# current_sense.net
KiCad netlist of a schematic drawn in EAGLE
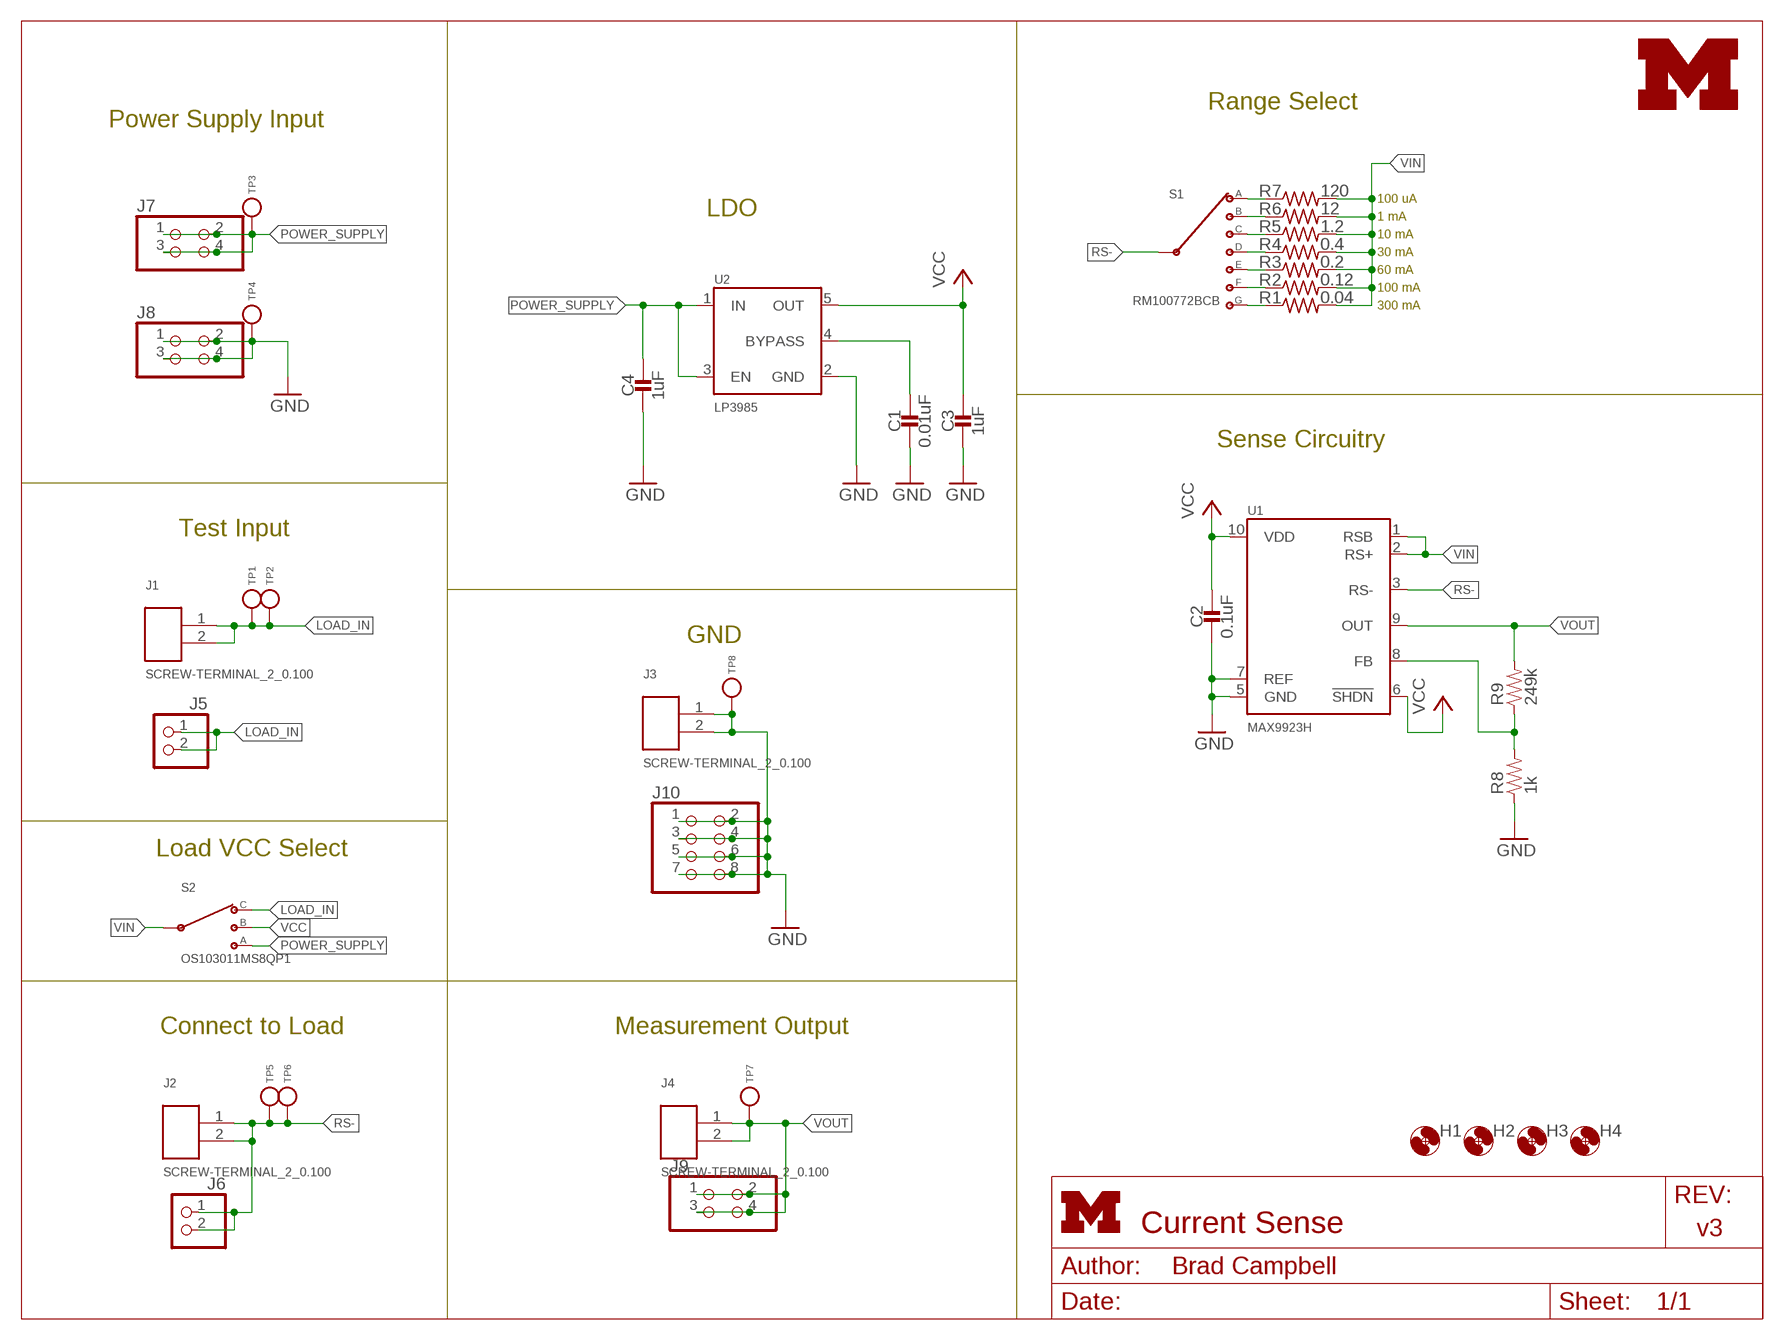
[diagram p0: schematic, sheet 1]

(export (version "E")
  (design (tool "Eeschema 10.0.6"))
  (components
    (comp (ref "C1")
      (value "0.01uF")
      (footprint "eagle-import:0603_CAP")
      (libsource (lib "eagle-import") (part "CAPACITOR0603_CAP"))
    )
    (comp (ref "C2")
      (value "0.1uF")
      (footprint "eagle-import:0603_CAP")
      (libsource (lib "eagle-import") (part "CAPACITOR0603_CAP"))
    )
    (comp (ref "C3")
      (value "1uF")
      (footprint "eagle-import:0603_CAP")
      (libsource (lib "eagle-import") (part "CAPACITOR0603_CAP"))
    )
    (comp (ref "C4")
      (value "1uF")
      (footprint "eagle-import:0603_CAP")
      (libsource (lib "eagle-import") (part "CAPACITOR0603_CAP"))
    )
    (comp (ref "H1")
      (value "MOUNT-HOLE3.2")
      (footprint "eagle-import:3,2")
      (libsource (lib "eagle-import") (part "MOUNT-HOLE3.2"))
    )
    (comp (ref "H2")
      (value "MOUNT-HOLE3.2")
      (footprint "eagle-import:3,2")
      (libsource (lib "eagle-import") (part "MOUNT-HOLE3.2"))
    )
    (comp (ref "H3")
      (value "MOUNT-HOLE3.2")
      (footprint "eagle-import:3,2")
      (libsource (lib "eagle-import") (part "MOUNT-HOLE3.2"))
    )
    (comp (ref "H4")
      (value "MOUNT-HOLE3.2")
      (footprint "eagle-import:3,2")
      (libsource (lib "eagle-import") (part "MOUNT-HOLE3.2"))
    )
    (comp (ref "J1")
      (value "SCREW-TERMINAL_2_0.100")
      (footprint "eagle-import:CONN_BLOCK_2")
      (libsource (lib "eagle-import") (part "SCREW-TERMINAL_2_0.100"))
    )
    (comp (ref "J2")
      (value "SCREW-TERMINAL_2_0.100")
      (footprint "eagle-import:CONN_BLOCK_2")
      (libsource (lib "eagle-import") (part "SCREW-TERMINAL_2_0.100"))
    )
    (comp (ref "J3")
      (value "SCREW-TERMINAL_2_0.100")
      (footprint "eagle-import:CONN_BLOCK_2")
      (libsource (lib "eagle-import") (part "SCREW-TERMINAL_2_0.100"))
    )
    (comp (ref "J4")
      (value "SCREW-TERMINAL_2_0.100")
      (footprint "eagle-import:CONN_BLOCK_2")
      (libsource (lib "eagle-import") (part "SCREW-TERMINAL_2_0.100"))
    )
    (comp (ref "J5")
      (value "PINHD-1X2")
      (footprint "eagle-import:1X02")
      (libsource (lib "eagle-import") (part "PINHD-1X2"))
    )
    (comp (ref "J6")
      (value "PINHD-1X2")
      (footprint "eagle-import:1X02")
      (libsource (lib "eagle-import") (part "PINHD-1X2"))
    )
    (comp (ref "J7")
      (value "PINHD-2X2")
      (footprint "eagle-import:2X02")
      (libsource (lib "eagle-import") (part "PINHD-2X2"))
    )
    (comp (ref "J8")
      (value "PINHD-2X2")
      (footprint "eagle-import:2X02")
      (libsource (lib "eagle-import") (part "PINHD-2X2"))
    )
    (comp (ref "J9")
      (value "PINHD-2X2")
      (footprint "eagle-import:2X02")
      (libsource (lib "eagle-import") (part "PINHD-2X2"))
    )
    (comp (ref "J10")
      (value "PINHD-2X4")
      (footprint "eagle-import:2X04")
      (libsource (lib "eagle-import") (part "PINHD-2X4"))
    )
    (comp (ref "LOGO2")
      (value "UMICH_SOLID_MEDIUM")
      (footprint "eagle-import:UMICH_SOLID_200MIL")
      (libsource (lib "eagle-import") (part "UMICH_SOLID_MEDIUM"))
    )
    (comp (ref "R1")
      (value "0.04")
      (footprint "eagle-import:R1206")
      (libsource (lib "eagle-import") (part "R-US_R1206"))
    )
    (comp (ref "R2")
      (value "0.12")
      (footprint "eagle-import:R1206")
      (libsource (lib "eagle-import") (part "R-US_R1206"))
    )
    (comp (ref "R3")
      (value "0.2")
      (footprint "eagle-import:R1206")
      (libsource (lib "eagle-import") (part "R-US_R1206"))
    )
    (comp (ref "R4")
      (value "0.4")
      (footprint "eagle-import:R1206")
      (libsource (lib "eagle-import") (part "R-US_R1206"))
    )
    (comp (ref "R5")
      (value "1.2")
      (footprint "eagle-import:R0805")
      (libsource (lib "eagle-import") (part "R-US_R0805"))
    )
    (comp (ref "R6")
      (value "12")
      (footprint "eagle-import:R0805")
      (libsource (lib "eagle-import") (part "R-US_R0805"))
    )
    (comp (ref "R7")
      (value "120")
      (footprint "eagle-import:R0805")
      (libsource (lib "eagle-import") (part "R-US_R0805"))
    )
    (comp (ref "R8")
      (value "1k")
      (footprint "eagle-import:0603-RES")
      (libsource (lib "eagle-import") (part "RESISTOR0603_RES"))
    )
    (comp (ref "R9")
      (value "249k")
      (footprint "eagle-import:0603-RES")
      (libsource (lib "eagle-import") (part "RESISTOR0603_RES"))
    )
    (comp (ref "S1")
      (value "RM100772BCB")
      (footprint "eagle-import:RM-SWITCH")
      (libsource (lib "eagle-import") (part "RM100772BCB"))
    )
    (comp (ref "S2")
      (value "OS103011MS8QP1")
      (footprint "eagle-import:OS102011MS8QP1")
      (libsource (lib "eagle-import") (part "OS103011MS8QP1"))
    )
    (comp (ref "TP1")
      (value "TEST_POINT_0.040IN")
      (footprint "eagle-import:TESTPOINT_0.040IN")
      (libsource (lib "eagle-import") (part "TEST_POINT_0.040IN"))
    )
    (comp (ref "TP2")
      (value "TEST_POINT_0.040IN")
      (footprint "eagle-import:TESTPOINT_0.040IN")
      (libsource (lib "eagle-import") (part "TEST_POINT_0.040IN"))
    )
    (comp (ref "TP3")
      (value "TEST_POINT_0.040IN")
      (footprint "eagle-import:TESTPOINT_0.040IN")
      (libsource (lib "eagle-import") (part "TEST_POINT_0.040IN"))
    )
    (comp (ref "TP4")
      (value "TEST_POINT_0.040IN")
      (footprint "eagle-import:TESTPOINT_0.040IN")
      (libsource (lib "eagle-import") (part "TEST_POINT_0.040IN"))
    )
    (comp (ref "TP5")
      (value "TEST_POINT_0.040IN")
      (footprint "eagle-import:TESTPOINT_0.040IN")
      (libsource (lib "eagle-import") (part "TEST_POINT_0.040IN"))
    )
    (comp (ref "TP6")
      (value "TEST_POINT_0.040IN")
      (footprint "eagle-import:TESTPOINT_0.040IN")
      (libsource (lib "eagle-import") (part "TEST_POINT_0.040IN"))
    )
    (comp (ref "TP7")
      (value "TEST_POINT_0.040IN")
      (footprint "eagle-import:TESTPOINT_0.040IN")
      (libsource (lib "eagle-import") (part "TEST_POINT_0.040IN"))
    )
    (comp (ref "TP8")
      (value "TEST_POINT_0.112IN")
      (footprint "eagle-import:TESTPOINT_0.112IN")
      (libsource (lib "eagle-import") (part "TEST_POINT_0.112IN"))
    )
    (comp (ref "U1")
      (value "MAX9923H")
      (footprint "eagle-import:UMAX10")
      (fields (field (name "DIGIKEY") "MAX9922EUB+TCT-ND"))
      (libsource (lib "eagle-import") (part "MAX9923H"))
    )
    (comp (ref "U2")
      (value "LP3985")
      (footprint "eagle-import:R-PDSO-G5")
      (libsource (lib "eagle-import") (part "LP3985"))
    )
  )
  (nets
    (net (code "1") (name "GND") (class "Default")
      (node (ref "C1") (pin "2") (pinfunction "2_2") (pintype "bidirectional"))
      (node (ref "C2") (pin "2") (pinfunction "2_2") (pintype "bidirectional"))
      (node (ref "C3") (pin "2") (pinfunction "2_2") (pintype "bidirectional"))
      (node (ref "C4") (pin "2") (pinfunction "2_2") (pintype "bidirectional"))
      (node (ref "J10") (pin "1") (pinfunction "1_1") (pintype "passive"))
      (node (ref "J10") (pin "2") (pinfunction "2_2") (pintype "passive"))
      (node (ref "J10") (pin "3") (pinfunction "3_3") (pintype "passive"))
      (node (ref "J10") (pin "4") (pinfunction "4_4") (pintype "passive"))
      (node (ref "J10") (pin "5") (pinfunction "5_5") (pintype "passive"))
      (node (ref "J10") (pin "6") (pinfunction "6_6") (pintype "passive"))
      (node (ref "J10") (pin "7") (pinfunction "7_7") (pintype "passive"))
      (node (ref "J10") (pin "8") (pinfunction "8_8") (pintype "passive"))
      (node (ref "J3") (pin "1") (pinfunction "1_1") (pintype "bidirectional"))
      (node (ref "J3") (pin "2") (pinfunction "2_2") (pintype "bidirectional"))
      (node (ref "J8") (pin "1") (pinfunction "1_1") (pintype "passive"))
      (node (ref "J8") (pin "2") (pinfunction "2_2") (pintype "passive"))
      (node (ref "J8") (pin "3") (pinfunction "3_3") (pintype "passive"))
      (node (ref "J8") (pin "4") (pinfunction "4_4") (pintype "passive"))
      (node (ref "R8") (pin "1") (pinfunction "1_1") (pintype "passive"))
      (node (ref "TP4") (pin "TESTPOINT") (pinfunction "TESTPOINT_TESTPOINT") (pintype "bidirectional"))
      (node (ref "TP8") (pin "1") (pinfunction "TESTPOINT_1") (pintype "bidirectional"))
      (node (ref "U1") (pin "5") (pinfunction "GND_5") (pintype "bidirectional"))
      (node (ref "U1") (pin "7") (pinfunction "REF_7") (pintype "bidirectional"))
      (node (ref "U2") (pin "2") (pinfunction "GND_2") (pintype "bidirectional"))
    )
    (net (code "2") (name "LOAD_IN") (class "Default")
      (node (ref "J1") (pin "1") (pinfunction "1_1") (pintype "bidirectional"))
      (node (ref "J1") (pin "2") (pinfunction "2_2") (pintype "bidirectional"))
      (node (ref "J5") (pin "1") (pinfunction "1_1") (pintype "passive"))
      (node (ref "J5") (pin "2") (pinfunction "2_2") (pintype "passive"))
      (node (ref "S2") (pin "4") (pinfunction "3_4") (pintype "bidirectional"))
      (node (ref "TP1") (pin "TESTPOINT") (pinfunction "TESTPOINT_TESTPOINT") (pintype "bidirectional"))
      (node (ref "TP2") (pin "TESTPOINT") (pinfunction "TESTPOINT_TESTPOINT") (pintype "bidirectional"))
    )
    (net (code "3") (name "Net-(S1-A)") (class "Default")
      (node (ref "R7") (pin "1") (pinfunction "1_1") (pintype "passive"))
      (node (ref "S1") (pin "1") (pinfunction "A_1") (pintype "bidirectional"))
    )
    (net (code "4") (name "Net-(S1-B)") (class "Default")
      (node (ref "R6") (pin "1") (pinfunction "1_1") (pintype "passive"))
      (node (ref "S1") (pin "2") (pinfunction "B_2") (pintype "bidirectional"))
    )
    (net (code "5") (name "Net-(S1-C)") (class "Default")
      (node (ref "R5") (pin "1") (pinfunction "1_1") (pintype "passive"))
      (node (ref "S1") (pin "3") (pinfunction "C_3") (pintype "bidirectional"))
    )
    (net (code "6") (name "Net-(S1-D)") (class "Default")
      (node (ref "R4") (pin "1") (pinfunction "1_1") (pintype "passive"))
      (node (ref "S1") (pin "4") (pinfunction "D_4") (pintype "bidirectional"))
    )
    (net (code "7") (name "Net-(S1-E)") (class "Default")
      (node (ref "R3") (pin "1") (pinfunction "1_1") (pintype "passive"))
      (node (ref "S1") (pin "5") (pinfunction "E_5") (pintype "bidirectional"))
    )
    (net (code "8") (name "Net-(S1-F)") (class "Default")
      (node (ref "R2") (pin "1") (pinfunction "1_1") (pintype "passive"))
      (node (ref "S1") (pin "6") (pinfunction "F_6") (pintype "bidirectional"))
    )
    (net (code "9") (name "Net-(S1-G)") (class "Default")
      (node (ref "R1") (pin "1") (pinfunction "1_1") (pintype "passive"))
      (node (ref "S1") (pin "7") (pinfunction "G_7") (pintype "bidirectional"))
    )
    (net (code "10") (name "Net-(U1-FB)") (class "Default")
      (node (ref "R8") (pin "2") (pinfunction "2_2") (pintype "passive"))
      (node (ref "R9") (pin "1") (pinfunction "1_1") (pintype "passive"))
      (node (ref "U1") (pin "8") (pinfunction "FB_8") (pintype "bidirectional"))
    )
    (net (code "11") (name "Net-(U2-BYPASS)") (class "Default")
      (node (ref "C1") (pin "1") (pinfunction "1_1") (pintype "bidirectional"))
      (node (ref "U2") (pin "4") (pinfunction "BYPASS_4") (pintype "bidirectional"))
    )
    (net (code "12") (name "POWER_SUPPLY") (class "Default")
      (node (ref "C4") (pin "1") (pinfunction "1_1") (pintype "bidirectional"))
      (node (ref "J7") (pin "1") (pinfunction "1_1") (pintype "passive"))
      (node (ref "J7") (pin "2") (pinfunction "2_2") (pintype "passive"))
      (node (ref "J7") (pin "3") (pinfunction "3_3") (pintype "passive"))
      (node (ref "J7") (pin "4") (pinfunction "4_4") (pintype "passive"))
      (node (ref "S2") (pin "1") (pinfunction "1_1") (pintype "bidirectional"))
      (node (ref "TP3") (pin "TESTPOINT") (pinfunction "TESTPOINT_TESTPOINT") (pintype "bidirectional"))
      (node (ref "U2") (pin "1") (pinfunction "IN_1") (pintype "bidirectional"))
      (node (ref "U2") (pin "3") (pinfunction "EN_3") (pintype "bidirectional"))
    )
    (net (code "13") (name "RS-") (class "Default")
      (node (ref "J2") (pin "1") (pinfunction "1_1") (pintype "bidirectional"))
      (node (ref "J2") (pin "2") (pinfunction "2_2") (pintype "bidirectional"))
      (node (ref "J6") (pin "1") (pinfunction "1_1") (pintype "passive"))
      (node (ref "J6") (pin "2") (pinfunction "2_2") (pintype "passive"))
      (node (ref "S1") (pin "C") (pinfunction "INPUT_C") (pintype "bidirectional"))
      (node (ref "TP5") (pin "TESTPOINT") (pinfunction "TESTPOINT_TESTPOINT") (pintype "bidirectional"))
      (node (ref "TP6") (pin "TESTPOINT") (pinfunction "TESTPOINT_TESTPOINT") (pintype "bidirectional"))
      (node (ref "U1") (pin "3") (pinfunction "RS-_3") (pintype "bidirectional"))
    )
    (net (code "14") (name "VCC") (class "Default")
      (node (ref "C2") (pin "1") (pinfunction "1_1") (pintype "bidirectional"))
      (node (ref "C3") (pin "1") (pinfunction "1_1") (pintype "bidirectional"))
      (node (ref "S2") (pin "3") (pinfunction "2_3") (pintype "bidirectional"))
      (node (ref "U1") (pin "10") (pinfunction "VDD_10") (pintype "bidirectional"))
      (node (ref "U1") (pin "6") (pinfunction "~{SHDN}_6") (pintype "bidirectional"))
      (node (ref "U2") (pin "5") (pinfunction "OUT_5") (pintype "bidirectional"))
    )
    (net (code "15") (name "VIN") (class "Default")
      (node (ref "R1") (pin "2") (pinfunction "2_2") (pintype "passive"))
      (node (ref "R2") (pin "2") (pinfunction "2_2") (pintype "passive"))
      (node (ref "R3") (pin "2") (pinfunction "2_2") (pintype "passive"))
      (node (ref "R4") (pin "2") (pinfunction "2_2") (pintype "passive"))
      (node (ref "R5") (pin "2") (pinfunction "2_2") (pintype "passive"))
      (node (ref "R6") (pin "2") (pinfunction "2_2") (pintype "passive"))
      (node (ref "R7") (pin "2") (pinfunction "2_2") (pintype "passive"))
      (node (ref "S2") (pin "2") (pinfunction "C_2") (pintype "bidirectional"))
      (node (ref "U1") (pin "1") (pinfunction "RSB_1") (pintype "bidirectional"))
      (node (ref "U1") (pin "2") (pinfunction "RS+_2") (pintype "bidirectional"))
    )
    (net (code "16") (name "VOUT") (class "Default")
      (node (ref "J4") (pin "1") (pinfunction "1_1") (pintype "bidirectional"))
      (node (ref "J4") (pin "2") (pinfunction "2_2") (pintype "bidirectional"))
      (node (ref "J9") (pin "1") (pinfunction "1_1") (pintype "passive"))
      (node (ref "J9") (pin "2") (pinfunction "2_2") (pintype "passive"))
      (node (ref "J9") (pin "3") (pinfunction "3_3") (pintype "passive"))
      (node (ref "J9") (pin "4") (pinfunction "4_4") (pintype "passive"))
      (node (ref "R9") (pin "2") (pinfunction "2_2") (pintype "passive"))
      (node (ref "TP7") (pin "TESTPOINT") (pinfunction "TESTPOINT_TESTPOINT") (pintype "bidirectional"))
      (node (ref "U1") (pin "9") (pinfunction "OUT_9") (pintype "bidirectional"))
    )
  )
)
